# tdc7201support.net
KiCad netlist of a schematic drawn in EAGLE
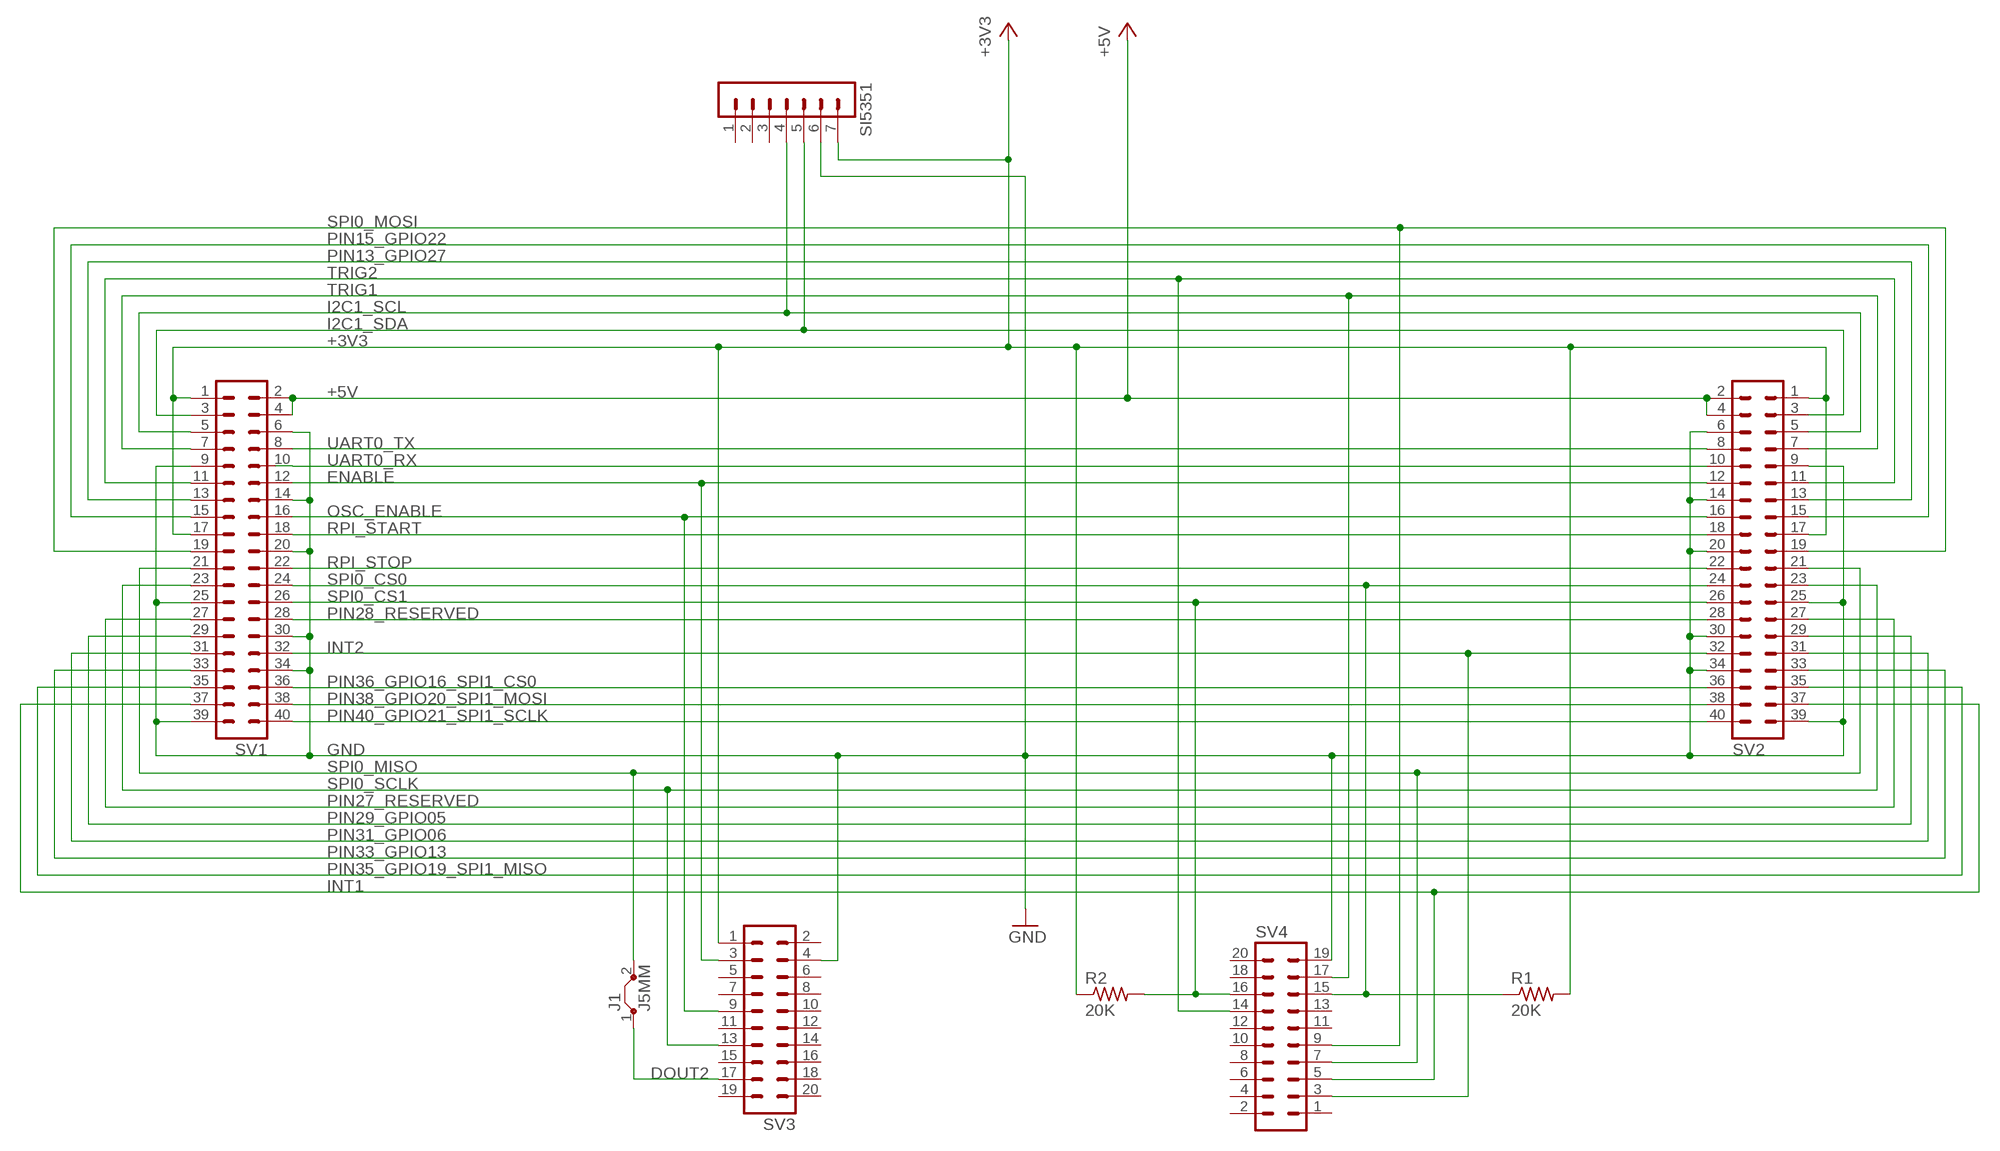
[diagram p0: schematic, sheet 1]

(export (version "E")
  (design (tool "Eeschema 10.0.6"))
  (components
    (comp (ref "J1")
      (value "J5MM")
      (footprint "eagle-import:05")
      (libsource (lib "eagle-import") (part "J5MM"))
    )
    (comp (ref "R1")
      (value "20K")
      (footprint "eagle-import:0617_22")
      (libsource (lib "eagle-import") (part "R-US_0617/22"))
    )
    (comp (ref "R2")
      (value "20K")
      (footprint "eagle-import:0617_22")
      (libsource (lib "eagle-import") (part "R-US_0617/22"))
    )
    (comp (ref "SI5351")
      (value "MA07-1")
      (footprint "eagle-import:MA07-1")
      (libsource (lib "eagle-import") (part "MA07-1"))
    )
    (comp (ref "SV1")
      (value "MA20-2")
      (footprint "eagle-import:MA20-2")
      (libsource (lib "eagle-import") (part "MA20-2"))
    )
    (comp (ref "SV2")
      (value "MA20-2")
      (footprint "eagle-import:MA20-2")
      (libsource (lib "eagle-import") (part "MA20-2"))
    )
    (comp (ref "SV3")
      (value "MA10-2")
      (footprint "eagle-import:MA10-2")
      (libsource (lib "eagle-import") (part "MA10-2"))
    )
    (comp (ref "SV4")
      (value "MA10-2")
      (footprint "eagle-import:MA10-2")
      (libsource (lib "eagle-import") (part "MA10-2"))
    )
  )
  (nets
    (net (code "1") (name "+3V3") (class "Default")
      (node (ref "R1") (pin "2") (pinfunction "2_2") (pintype "passive"))
      (node (ref "R2") (pin "1") (pinfunction "1_1") (pintype "passive"))
      (node (ref "SI5351") (pin "7") (pinfunction "7_7") (pintype "passive"))
      (node (ref "SV1") (pin "1") (pinfunction "1_1") (pintype "passive"))
      (node (ref "SV1") (pin "17") (pinfunction "17_17") (pintype "passive"))
      (node (ref "SV2") (pin "1") (pinfunction "1_1") (pintype "passive"))
      (node (ref "SV2") (pin "17") (pinfunction "17_17") (pintype "passive"))
      (node (ref "SV3") (pin "1") (pinfunction "1_1") (pintype "passive"))
    )
    (net (code "2") (name "+5V") (class "Default")
      (node (ref "SV1") (pin "2") (pinfunction "2_2") (pintype "passive"))
      (node (ref "SV1") (pin "4") (pinfunction "4_4") (pintype "passive"))
      (node (ref "SV2") (pin "2") (pinfunction "2_2") (pintype "passive"))
      (node (ref "SV2") (pin "4") (pinfunction "4_4") (pintype "passive"))
    )
    (net (code "3") (name "/DOUT2") (class "Default")
      (node (ref "J1") (pin "1") (pinfunction "1_1") (pintype "passive"))
      (node (ref "SV3") (pin "17") (pinfunction "17_17") (pintype "passive"))
    )
    (net (code "4") (name "/ENABLE") (class "Default")
      (node (ref "SV1") (pin "12") (pinfunction "12_12") (pintype "passive"))
      (node (ref "SV2") (pin "12") (pinfunction "12_12") (pintype "passive"))
      (node (ref "SV3") (pin "3") (pinfunction "3_3") (pintype "passive"))
    )
    (net (code "5") (name "/I2C1_SCL") (class "Default")
      (node (ref "SI5351") (pin "4") (pinfunction "4_4") (pintype "passive"))
      (node (ref "SV1") (pin "5") (pinfunction "5_5") (pintype "passive"))
      (node (ref "SV2") (pin "5") (pinfunction "5_5") (pintype "passive"))
    )
    (net (code "6") (name "/I2C1_SDA") (class "Default")
      (node (ref "SI5351") (pin "5") (pinfunction "5_5") (pintype "passive"))
      (node (ref "SV1") (pin "3") (pinfunction "3_3") (pintype "passive"))
      (node (ref "SV2") (pin "3") (pinfunction "3_3") (pintype "passive"))
    )
    (net (code "7") (name "/INT1") (class "Default")
      (node (ref "SV1") (pin "37") (pinfunction "37_37") (pintype "passive"))
      (node (ref "SV2") (pin "37") (pinfunction "37_37") (pintype "passive"))
      (node (ref "SV4") (pin "5") (pinfunction "5_5") (pintype "passive"))
    )
    (net (code "8") (name "/INT2") (class "Default")
      (node (ref "SV1") (pin "32") (pinfunction "32_32") (pintype "passive"))
      (node (ref "SV2") (pin "32") (pinfunction "32_32") (pintype "passive"))
      (node (ref "SV4") (pin "3") (pinfunction "3_3") (pintype "passive"))
    )
    (net (code "9") (name "/OSC_ENABLE") (class "Default")
      (node (ref "SV1") (pin "16") (pinfunction "16_16") (pintype "passive"))
      (node (ref "SV2") (pin "16") (pinfunction "16_16") (pintype "passive"))
      (node (ref "SV3") (pin "9") (pinfunction "9_9") (pintype "passive"))
    )
    (net (code "10") (name "/PIN13_GPIO27") (class "Default")
      (node (ref "SV1") (pin "13") (pinfunction "13_13") (pintype "passive"))
      (node (ref "SV2") (pin "13") (pinfunction "13_13") (pintype "passive"))
    )
    (net (code "11") (name "/PIN15_GPIO22") (class "Default")
      (node (ref "SV1") (pin "15") (pinfunction "15_15") (pintype "passive"))
      (node (ref "SV2") (pin "15") (pinfunction "15_15") (pintype "passive"))
    )
    (net (code "12") (name "/PIN27_RESERVED") (class "Default")
      (node (ref "SV1") (pin "27") (pinfunction "27_27") (pintype "passive"))
      (node (ref "SV2") (pin "27") (pinfunction "27_27") (pintype "passive"))
    )
    (net (code "13") (name "/PIN28_RESERVED") (class "Default")
      (node (ref "SV1") (pin "28") (pinfunction "28_28") (pintype "passive"))
      (node (ref "SV2") (pin "28") (pinfunction "28_28") (pintype "passive"))
    )
    (net (code "14") (name "/PIN29_GPIO05") (class "Default")
      (node (ref "SV1") (pin "29") (pinfunction "29_29") (pintype "passive"))
      (node (ref "SV2") (pin "29") (pinfunction "29_29") (pintype "passive"))
    )
    (net (code "15") (name "/PIN31_GPIO06") (class "Default")
      (node (ref "SV1") (pin "31") (pinfunction "31_31") (pintype "passive"))
      (node (ref "SV2") (pin "31") (pinfunction "31_31") (pintype "passive"))
    )
    (net (code "16") (name "/PIN33_GPIO13") (class "Default")
      (node (ref "SV1") (pin "33") (pinfunction "33_33") (pintype "passive"))
      (node (ref "SV2") (pin "33") (pinfunction "33_33") (pintype "passive"))
    )
    (net (code "17") (name "/PIN35_GPIO19_SPI1_MISO") (class "Default")
      (node (ref "SV1") (pin "35") (pinfunction "35_35") (pintype "passive"))
      (node (ref "SV2") (pin "35") (pinfunction "35_35") (pintype "passive"))
    )
    (net (code "18") (name "/PIN36_GPIO16_SPI1_CS0") (class "Default")
      (node (ref "SV1") (pin "36") (pinfunction "36_36") (pintype "passive"))
      (node (ref "SV2") (pin "36") (pinfunction "36_36") (pintype "passive"))
    )
    (net (code "19") (name "/PIN38_GPIO20_SPI1_MOSI") (class "Default")
      (node (ref "SV1") (pin "38") (pinfunction "38_38") (pintype "passive"))
      (node (ref "SV2") (pin "38") (pinfunction "38_38") (pintype "passive"))
    )
    (net (code "20") (name "/PIN40_GPIO21_SPI1_SCLK") (class "Default")
      (node (ref "SV1") (pin "40") (pinfunction "40_40") (pintype "passive"))
      (node (ref "SV2") (pin "40") (pinfunction "40_40") (pintype "passive"))
    )
    (net (code "21") (name "/RPI_START") (class "Default")
      (node (ref "SV1") (pin "18") (pinfunction "18_18") (pintype "passive"))
      (node (ref "SV2") (pin "18") (pinfunction "18_18") (pintype "passive"))
    )
    (net (code "22") (name "/RPI_STOP") (class "Default")
      (node (ref "SV1") (pin "22") (pinfunction "22_22") (pintype "passive"))
      (node (ref "SV2") (pin "22") (pinfunction "22_22") (pintype "passive"))
    )
    (net (code "23") (name "/SPI0_CS0") (class "Default")
      (node (ref "R1") (pin "1") (pinfunction "1_1") (pintype "passive"))
      (node (ref "SV1") (pin "24") (pinfunction "24_24") (pintype "passive"))
      (node (ref "SV2") (pin "24") (pinfunction "24_24") (pintype "passive"))
      (node (ref "SV4") (pin "15") (pinfunction "15_15") (pintype "passive"))
    )
    (net (code "24") (name "/SPI0_CS1") (class "Default")
      (node (ref "R2") (pin "2") (pinfunction "2_2") (pintype "passive"))
      (node (ref "SV1") (pin "26") (pinfunction "26_26") (pintype "passive"))
      (node (ref "SV2") (pin "26") (pinfunction "26_26") (pintype "passive"))
      (node (ref "SV4") (pin "16") (pinfunction "16_16") (pintype "passive"))
    )
    (net (code "25") (name "/SPI0_MISO") (class "Default")
      (node (ref "J1") (pin "2") (pinfunction "2_2") (pintype "passive"))
      (node (ref "SV1") (pin "21") (pinfunction "21_21") (pintype "passive"))
      (node (ref "SV2") (pin "21") (pinfunction "21_21") (pintype "passive"))
      (node (ref "SV4") (pin "7") (pinfunction "7_7") (pintype "passive"))
    )
    (net (code "26") (name "/SPI0_MOSI") (class "Default")
      (node (ref "SV1") (pin "19") (pinfunction "19_19") (pintype "passive"))
      (node (ref "SV2") (pin "19") (pinfunction "19_19") (pintype "passive"))
      (node (ref "SV4") (pin "9") (pinfunction "9_9") (pintype "passive"))
    )
    (net (code "27") (name "/SPI0_SCLK") (class "Default")
      (node (ref "SV1") (pin "23") (pinfunction "23_23") (pintype "passive"))
      (node (ref "SV2") (pin "23") (pinfunction "23_23") (pintype "passive"))
      (node (ref "SV3") (pin "13") (pinfunction "13_13") (pintype "passive"))
    )
    (net (code "28") (name "/TRIG1") (class "Default")
      (node (ref "SV1") (pin "7") (pinfunction "7_7") (pintype "passive"))
      (node (ref "SV2") (pin "7") (pinfunction "7_7") (pintype "passive"))
      (node (ref "SV4") (pin "17") (pinfunction "17_17") (pintype "passive"))
    )
    (net (code "29") (name "/TRIG2") (class "Default")
      (node (ref "SV1") (pin "11") (pinfunction "11_11") (pintype "passive"))
      (node (ref "SV2") (pin "11") (pinfunction "11_11") (pintype "passive"))
      (node (ref "SV4") (pin "14") (pinfunction "14_14") (pintype "passive"))
    )
    (net (code "30") (name "/UART0_RX") (class "Default")
      (node (ref "SV1") (pin "10") (pinfunction "10_10") (pintype "passive"))
      (node (ref "SV2") (pin "10") (pinfunction "10_10") (pintype "passive"))
    )
    (net (code "31") (name "/UART0_TX") (class "Default")
      (node (ref "SV1") (pin "8") (pinfunction "8_8") (pintype "passive"))
      (node (ref "SV2") (pin "8") (pinfunction "8_8") (pintype "passive"))
    )
    (net (code "32") (name "GND") (class "Default")
      (node (ref "SI5351") (pin "6") (pinfunction "6_6") (pintype "passive"))
      (node (ref "SV1") (pin "14") (pinfunction "14_14") (pintype "passive"))
      (node (ref "SV1") (pin "20") (pinfunction "20_20") (pintype "passive"))
      (node (ref "SV1") (pin "25") (pinfunction "25_25") (pintype "passive"))
      (node (ref "SV1") (pin "30") (pinfunction "30_30") (pintype "passive"))
      (node (ref "SV1") (pin "34") (pinfunction "34_34") (pintype "passive"))
      (node (ref "SV1") (pin "39") (pinfunction "39_39") (pintype "passive"))
      (node (ref "SV1") (pin "6") (pinfunction "6_6") (pintype "passive"))
      (node (ref "SV1") (pin "9") (pinfunction "9_9") (pintype "passive"))
      (node (ref "SV2") (pin "14") (pinfunction "14_14") (pintype "passive"))
      (node (ref "SV2") (pin "20") (pinfunction "20_20") (pintype "passive"))
      (node (ref "SV2") (pin "25") (pinfunction "25_25") (pintype "passive"))
      (node (ref "SV2") (pin "30") (pinfunction "30_30") (pintype "passive"))
      (node (ref "SV2") (pin "34") (pinfunction "34_34") (pintype "passive"))
      (node (ref "SV2") (pin "39") (pinfunction "39_39") (pintype "passive"))
      (node (ref "SV2") (pin "6") (pinfunction "6_6") (pintype "passive"))
      (node (ref "SV2") (pin "9") (pinfunction "9_9") (pintype "passive"))
      (node (ref "SV3") (pin "4") (pinfunction "4_4") (pintype "passive"))
      (node (ref "SV4") (pin "19") (pinfunction "19_19") (pintype "passive"))
    )
    (net (code "33") (name "unconnected-(SI5351-Pad1)") (class "Default")
      (node (ref "SI5351") (pin "1") (pinfunction "1_1") (pintype "passive"))
    )
    (net (code "34") (name "unconnected-(SI5351-Pad2)") (class "Default")
      (node (ref "SI5351") (pin "2") (pinfunction "2_2") (pintype "passive"))
    )
    (net (code "35") (name "unconnected-(SI5351-Pad3)") (class "Default")
      (node (ref "SI5351") (pin "3") (pinfunction "3_3") (pintype "passive"))
    )
    (net (code "36") (name "unconnected-(SV3-Pad2)") (class "Default")
      (node (ref "SV3") (pin "2") (pinfunction "2_2") (pintype "passive"))
    )
    (net (code "37") (name "unconnected-(SV3-Pad5)") (class "Default")
      (node (ref "SV3") (pin "5") (pinfunction "5_5") (pintype "passive"))
    )
    (net (code "38") (name "unconnected-(SV3-Pad6)") (class "Default")
      (node (ref "SV3") (pin "6") (pinfunction "6_6") (pintype "passive"))
    )
    (net (code "39") (name "unconnected-(SV3-Pad7)") (class "Default")
      (node (ref "SV3") (pin "7") (pinfunction "7_7") (pintype "passive"))
    )
    (net (code "40") (name "unconnected-(SV3-Pad8)") (class "Default")
      (node (ref "SV3") (pin "8") (pinfunction "8_8") (pintype "passive"))
    )
    (net (code "41") (name "unconnected-(SV3-Pad10)") (class "Default")
      (node (ref "SV3") (pin "10") (pinfunction "10_10") (pintype "passive"))
    )
    (net (code "42") (name "unconnected-(SV3-Pad11)") (class "Default")
      (node (ref "SV3") (pin "11") (pinfunction "11_11") (pintype "passive"))
    )
    (net (code "43") (name "unconnected-(SV3-Pad12)") (class "Default")
      (node (ref "SV3") (pin "12") (pinfunction "12_12") (pintype "passive"))
    )
    (net (code "44") (name "unconnected-(SV3-Pad14)") (class "Default")
      (node (ref "SV3") (pin "14") (pinfunction "14_14") (pintype "passive"))
    )
    (net (code "45") (name "unconnected-(SV3-Pad15)") (class "Default")
      (node (ref "SV3") (pin "15") (pinfunction "15_15") (pintype "passive"))
    )
    (net (code "46") (name "unconnected-(SV3-Pad16)") (class "Default")
      (node (ref "SV3") (pin "16") (pinfunction "16_16") (pintype "passive"))
    )
    (net (code "47") (name "unconnected-(SV3-Pad18)") (class "Default")
      (node (ref "SV3") (pin "18") (pinfunction "18_18") (pintype "passive"))
    )
    (net (code "48") (name "unconnected-(SV3-Pad19)") (class "Default")
      (node (ref "SV3") (pin "19") (pinfunction "19_19") (pintype "passive"))
    )
    (net (code "49") (name "unconnected-(SV3-Pad20)") (class "Default")
      (node (ref "SV3") (pin "20") (pinfunction "20_20") (pintype "passive"))
    )
    (net (code "50") (name "unconnected-(SV4-Pad1)") (class "Default")
      (node (ref "SV4") (pin "1") (pinfunction "1_1") (pintype "passive"))
    )
    (net (code "51") (name "unconnected-(SV4-Pad2)") (class "Default")
      (node (ref "SV4") (pin "2") (pinfunction "2_2") (pintype "passive"))
    )
    (net (code "52") (name "unconnected-(SV4-Pad4)") (class "Default")
      (node (ref "SV4") (pin "4") (pinfunction "4_4") (pintype "passive"))
    )
    (net (code "53") (name "unconnected-(SV4-Pad6)") (class "Default")
      (node (ref "SV4") (pin "6") (pinfunction "6_6") (pintype "passive"))
    )
    (net (code "54") (name "unconnected-(SV4-Pad8)") (class "Default")
      (node (ref "SV4") (pin "8") (pinfunction "8_8") (pintype "passive"))
    )
    (net (code "55") (name "unconnected-(SV4-Pad10)") (class "Default")
      (node (ref "SV4") (pin "10") (pinfunction "10_10") (pintype "passive"))
    )
    (net (code "56") (name "unconnected-(SV4-Pad11)") (class "Default")
      (node (ref "SV4") (pin "11") (pinfunction "11_11") (pintype "passive"))
    )
    (net (code "57") (name "unconnected-(SV4-Pad12)") (class "Default")
      (node (ref "SV4") (pin "12") (pinfunction "12_12") (pintype "passive"))
    )
    (net (code "58") (name "unconnected-(SV4-Pad13)") (class "Default")
      (node (ref "SV4") (pin "13") (pinfunction "13_13") (pintype "passive"))
    )
    (net (code "59") (name "unconnected-(SV4-Pad18)") (class "Default")
      (node (ref "SV4") (pin "18") (pinfunction "18_18") (pintype "passive"))
    )
    (net (code "60") (name "unconnected-(SV4-Pad20)") (class "Default")
      (node (ref "SV4") (pin "20") (pinfunction "20_20") (pintype "passive"))
    )
  )
)
